# 5V_Main.net
KiCad netlist of a schematic drawn in Altium Designer
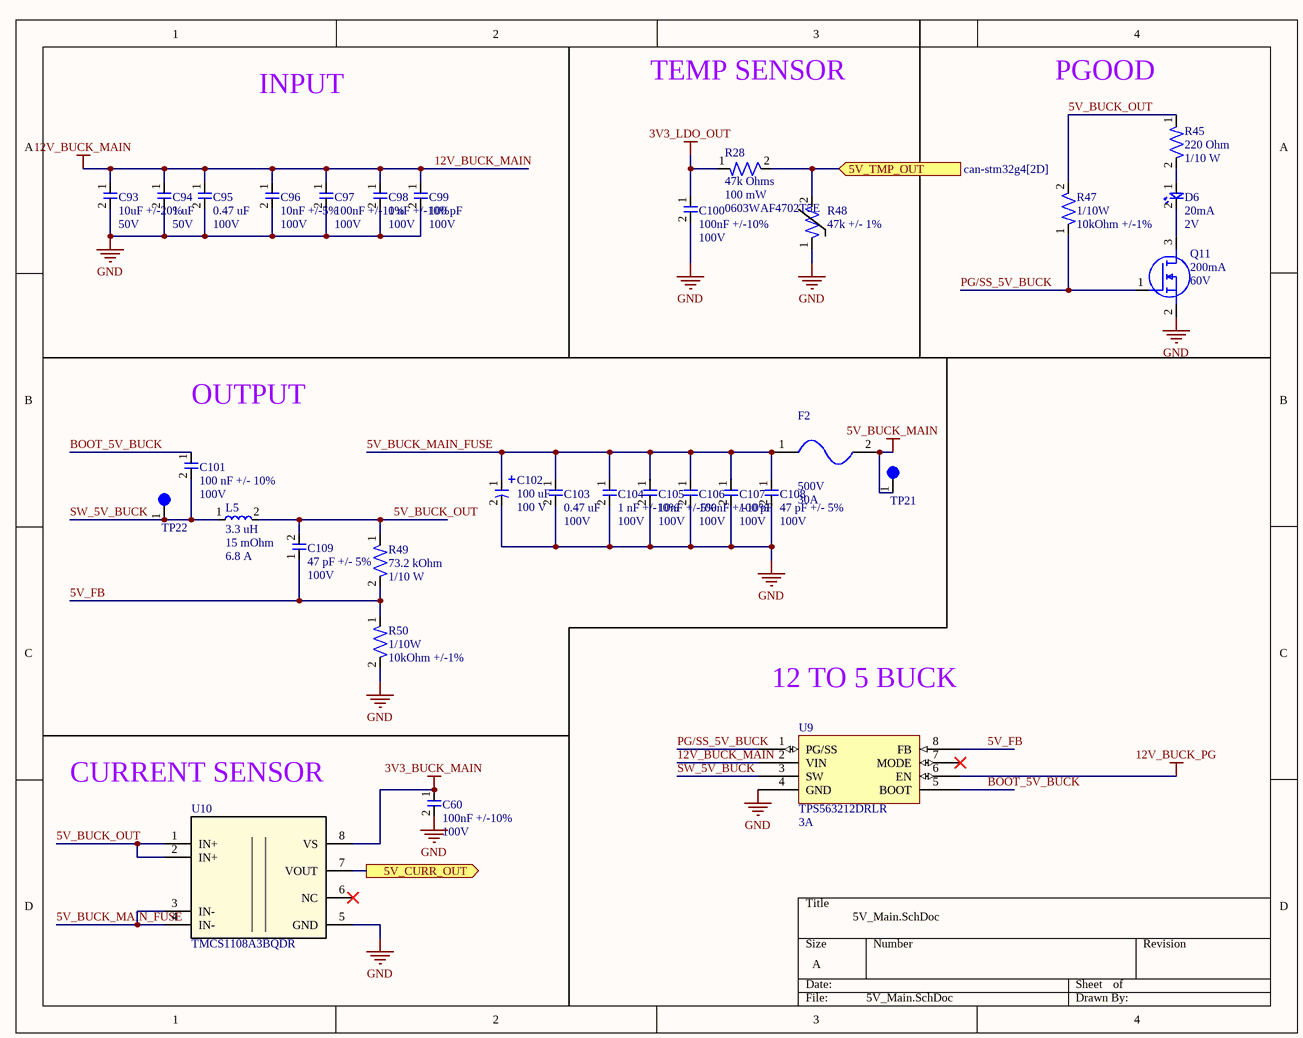
[diagram p0: 5V_Main.SchDoc]

(export (version "E")
  (design (tool "Eeschema 10.0.6"))
  (components
    (comp (ref "C60")
      (value "CC0603KRX7R0BB104")
      (footprint "CAP-0603")
      (description "CAP CER 0.1UF 100V X7R 0603")
      (fields
        (field (name "MANUFACTURER") "YAGEO")
        (field (name "CAPACITANCE") "100nF +/-10%")
        (field (name "VOLTAGE RATING") "100V")
      )
      (libsource (lib "MasterLib") (part "CAP-100N-0001"))
    )
    (comp (ref "C93")
      (value "CL31B106KBHNNNE")
      (footprint "CAP-1206")
      (description "10 µF ±10% 50V Ceramic Capacitor X7R 1206 (3216 Metric)")
      (fields
        (field (name "MANUFACTURER") "Samsung Electro-Mechanics")
        (field (name "CAPACITANCE") "10uF +/-20%")
        (field (name "VOLTAGE RATING") "50V")
      )
      (libsource (lib "MasterLib") (part "CAP-10U-0001"))
    )
    (comp (ref "C94")
      (value "UMK107AB7105KA-T")
      (footprint "CAP-0603")
      (description "1 µF ±10% 50V Ceramic Capacitor X7R 0603 (1608 Metric)")
      (fields (field (name "CAPACITANCE") "1 uF") (field (name "VOLTAGE") "50V"))
      (libsource (lib "MasterLib") (part "CAP-1U-0002"))
    )
    (comp (ref "C95")
      (value "KAM21KR72A474KL")
      (footprint "CAP-0805")
      (description "0.47 µF ±10% 100V Ceramic Capacitor X7R 0805 (2012 Metric)")
      (fields
        (field (name "TOLERANCE") "+/- 10%")
        (field (name "CAPACITANCE") "0.47 uF")
        (field (name "VOLTAGE") "100V")
      )
      (libsource (lib "MasterLib") (part "CAP-0.47U-0001"))
    )
    (comp (ref "C96")
      (value "C1608C0G2A103J080AC")
      (footprint "CAP-0603")
      (description "CAP CER 10000PF 100V C0G 0603")
      (fields
        (field (name "MANUFACTURER") "TDK Corporation")
        (field (name "CAPACITANCE") "10nF +/-5%")
        (field (name "VOLTAGE RATING") "100V")
      )
      (libsource (lib "MasterLib") (part "CAP-10N-0002"))
    )
    (comp (ref "C97")
      (value "CC0603KRX7R0BB104")
      (footprint "CAP-0603")
      (description "CAP CER 0.1UF 100V X7R 0603")
      (fields
        (field (name "MANUFACTURER") "YAGEO")
        (field (name "CAPACITANCE") "100nF +/-10%")
        (field (name "VOLTAGE RATING") "100V")
      )
      (libsource (lib "MasterLib") (part "CAP-100N-0001"))
    )
    (comp (ref "C98")
      (value "C0603Y102K1RAC7867")
      (footprint "CAP-0603")
      (description "1000 pF ±10% 100V Ceramic Capacitor X7R 0603 (1608 Metric)")
      (fields (field (name "CAPACITANCE") "1 nF +/-10%") (field (name "VOLTAGE") "100V"))
      (libsource (lib "MasterLib") (part "CAP-1N-0001"))
    )
    (comp (ref "C99")
      (value "0603N101J101CT")
      (footprint "CAP-0603")
      (description "100 pF ±5% 100V Ceramic Capacitor C0G, NP0 0603 (1608 Metric)")
      (fields
        (field (name "TOLERANCE") "+/-5%")
        (field (name "CAPACITANCE") "100 pF")
        (field (name "VOLTAGE") "100V")
      )
      (libsource (lib "MasterLib") (part "CAP-100P-0002"))
    )
    (comp (ref "C100")
      (value "CC0603KRX7R0BB104")
      (footprint "CAP-0603")
      (description "CAP CER 0.1UF 100V X7R 0603")
      (fields
        (field (name "MANUFACTURER") "YAGEO")
        (field (name "CAPACITANCE") "100nF +/-10%")
        (field (name "VOLTAGE RATING") "100V")
      )
      (libsource (lib "MasterLib") (part "CAP-100N-0001"))
    )
    (comp (ref "C101")
      (value "CC0603KRX7R0BB104")
      (footprint "CAP-0603")
      (description "100V 100nF X7R ±10% 0603 Multilayer Ceramic Capacitors MLCC - SMD/SMT ROHS")
      (fields
        (field (name "JLC PART NUMBER") "C113803")
        (field (name "CAPACITANCE") "100 nF +/- 10%")
        (field (name "VOLTAGE") "100V")
      )
      (libsource (lib "MasterLib") (part "CAP-100N-0002-JLC"))
    )
    (comp (ref "C102")
      (value "100SEV100M12.5X16")
      (footprint "ELEC-100U-0001")
      (description "100 µF 100 V Aluminum Electrolytic Capacitors Radial, Can - SMD 2000 Hrs @ 85°C")
      (fields
        (field (name "MANUFACTURER") "Rubycon")
        (field (name "TOLERANCE") "+/- 20%")
        (field (name "CAPACITANCE") "100 uF")
        (field (name "VOLTAGE") "100 V")
      )
      (libsource (lib "MasterLib") (part "ELEC-100U-0001"))
    )
    (comp (ref "C103")
      (value "KAM21KR72A474KL")
      (footprint "CAP-0805")
      (description "0.47 µF ±10% 100V Ceramic Capacitor X7R 0805 (2012 Metric)")
      (fields
        (field (name "TOLERANCE") "+/- 10%")
        (field (name "CAPACITANCE") "0.47 uF")
        (field (name "VOLTAGE") "100V")
      )
      (libsource (lib "MasterLib") (part "CAP-0.47U-0001"))
    )
    (comp (ref "C104")
      (value "C0603Y102K1RAC7867")
      (footprint "CAP-0603")
      (description "1000 pF ±10% 100V Ceramic Capacitor X7R 0603 (1608 Metric)")
      (fields (field (name "CAPACITANCE") "1 nF +/-10%") (field (name "VOLTAGE") "100V"))
      (libsource (lib "MasterLib") (part "CAP-1N-0001"))
    )
    (comp (ref "C105")
      (value "C1608C0G2A103J080AC")
      (footprint "CAP-0603")
      (description "CAP CER 10000PF 100V C0G 0603")
      (fields
        (field (name "MANUFACTURER") "TDK Corporation")
        (field (name "CAPACITANCE") "10nF +/-5%")
        (field (name "VOLTAGE RATING") "100V")
      )
      (libsource (lib "MasterLib") (part "CAP-10N-0002"))
    )
    (comp (ref "C106")
      (value "CC0603KRX7R0BB104")
      (footprint "CAP-0603")
      (description "CAP CER 0.1UF 100V X7R 0603")
      (fields
        (field (name "MANUFACTURER") "YAGEO")
        (field (name "CAPACITANCE") "100nF +/-10%")
        (field (name "VOLTAGE RATING") "100V")
      )
      (libsource (lib "MasterLib") (part "CAP-100N-0001"))
    )
    (comp (ref "C107")
      (value "0603N101J101CT")
      (footprint "CAP-0603")
      (description "100 pF ±5% 100V Ceramic Capacitor C0G, NP0 0603 (1608 Metric)")
      (fields
        (field (name "TOLERANCE") "+/-5%")
        (field (name "CAPACITANCE") "100 pF")
        (field (name "VOLTAGE") "100V")
      )
      (libsource (lib "MasterLib") (part "CAP-100P-0002"))
    )
    (comp (ref "C108")
      (value "7447798111")
      (footprint "CAP-0603")
      (description "47 pF ±5% 100V Ceramic Capacitor C0G, NP0 0603 (1608 Metric)")
      (fields (field (name "CAPACITANCE") "47 pF +/- 5%") (field (name "VOLTAGE RATING") "100V"))
      (libsource (lib "MasterLib") (part "CAP-47P-0001"))
    )
    (comp (ref "C109")
      (value "7447798111")
      (footprint "CAP-0603")
      (description "47 pF ±5% 100V Ceramic Capacitor C0G, NP0 0603 (1608 Metric)")
      (fields (field (name "CAPACITANCE") "47 pF +/- 5%") (field (name "VOLTAGE RATING") "100V"))
      (libsource (lib "MasterLib") (part "CAP-47P-0001"))
    )
    (comp (ref "D6")
      (value "150060AS75000")
      (footprint "LED-0603")
      (description "CAP CER 0.1UF 100V X7R 0603")
      (fields
        (field (name "MANUFACTURER") "Wurth Electronik")
        (field (name "CURRENT RATING") "20mA")
        (field (name "VF") "2V")
      )
      (libsource (lib "MasterLib") (part "LED_Amber_0001"))
    )
    (comp (ref "F2")
      (value "3568")
      (footprint "FUSE-ATM-0001")
      (description "Fuse Holder 30 A 500V 1 Circuit Blade Through Hole")
      (fields (field (name "VOLTAGE RATING") "500V") (field (name "CURRENT") "30A"))
      (libsource (lib "MasterLib") (part "FUSE-ATM-0001"))
    )
    (comp (ref "L5")
      (value "SRR1240-3R3Y")
      (footprint "PWRIND-3.3U-0003")
      (description "3.3 µH Shielded Drum Core, Wirewound Inductor 6.8 A 15mOhm Max Nonstandard")
      (fields
        (field (name "TOLERANCE") "30%")
        (field (name "INDUCTANCE") "3.3 uH")
        (field (name "DCR") "15 mOhm")
        (field (name "DCI") "6.8 A")
      )
      (libsource (lib "MasterLib") (part "PWRIND-3.3U-0003"))
    )
    (comp (ref "Q11")
      (value "T2N7002AK,LM")
      (footprint "NMOS-SOT23-3")
      (description "MOSFET N-CH 60V 200MA SOT23")
      (fields
        (field (name "MANUFACTURER") "Toshiba")
        (field (name "ID-CONTINUOUS") "200mA")
        (field (name "VDS-MAX") "60V")
      )
      (libsource (lib "MasterLib") (part "NMOS-200MA-0001"))
    )
    (comp (ref "R28")
      (value "0603WAF4702T5E")
      (footprint "RES-0603")
      (description "100mW Thick Film Resistors 75V ±100ppm/℃ ±1% 47kΩ 0603 Chip Resistor - Surface Mount ROHS")
      (fields (field (name "POWER") "100mW"))
      (libsource (lib "MasterLib") (part "RES-47k-0001-JLC"))
    )
    (comp (ref "R45")
      (value "CRGCQ0603J220R")
      (footprint "RES-0603")
      (fields
        (field (name "TOLERANCE") "+/- 5%")
        (field (name "RESISTANCE") "220 Ohm")
        (field (name "POWER") "1/10 W")
      )
      (libsource (lib "MasterLib") (part "RES-220-003"))
    )
    (comp (ref "R47")
      (value "RC0603FR-0710KP")
      (footprint "RES-0603")
      (description "RES SMD 10K OHM 1% 1/10W 0603")
      (fields
        (field (name "MANUFACTURER") "YAGEO")
        (field (name "POWER RATING") "1/10W")
        (field (name "RESISTANCE") "10kOhm +/-1%")
      )
      (libsource (lib "MasterLib") (part "RES-10K-0002"))
    )
    (comp (ref "R48")
      (value "TMP6431DECR")
      (footprint "RES-0402")
      (description "PTC Thermistor 47 kOhms 0402 (1006 Metric)")
      (fields (field (name "MANUFACTURER") "Texas Instruments") (field (name "RESISTANCE") "47k +/- 1%"))
      (libsource (lib "MasterLib") (part "THERM-47K-0001"))
    )
    (comp (ref "R49")
      (value "RC0603FR-0773K2L")
      (footprint "RES-0603")
      (description "73.2 kOhms ±1% 0.1W, 1/10W Chip Resistor 0603 (1608 Metric) Moisture Resistant Thick Film")
      (fields
        (field (name "TOLERANCE") "1%")
        (field (name "RESISTANCE") "73.2 kOhm")
        (field (name "POWER") "1/10 W")
      )
      (libsource (lib "MasterLib") (part "RES-73.2K-0001"))
    )
    (comp (ref "R50")
      (value "RC0603FR-0710KP")
      (footprint "RES-0603")
      (description "RES SMD 10K OHM 1% 1/10W 0603")
      (fields
        (field (name "MANUFACTURER") "YAGEO")
        (field (name "POWER RATING") "1/10W")
        (field (name "RESISTANCE") "10kOhm +/-1%")
      )
      (libsource (lib "MasterLib") (part "RES-10K-0002"))
    )
    (comp (ref "TP21")
      (value "5003")
      (footprint "TEST-POINT-0001")
      (description "Oranange PC Test Point, Miniature Phoisphor Bronze Silver Plating Through Hole Mounting Type")
      (libsource (lib "MasterLib") (part "TEST-POINT-0001"))
    )
    (comp (ref "TP22")
      (value "5003")
      (footprint "TEST-POINT-0001")
      (description "Oranange PC Test Point, Miniature Phoisphor Bronze Silver Plating Through Hole Mounting Type")
      (libsource (lib "MasterLib") (part "TEST-POINT-0001"))
    )
    (comp (ref "U9")
      (value "TPS563212DRLR")
      (footprint "IC-SOT583")
      (description "Buck Switching Regulator IC Positive Adjustable 0.6V 1 Output 3A SOT-583")
      (fields (field (name "MANUFACTURER") "Texaas Instruments") (field (name "CURRENT") "3A"))
      (libsource (lib "MasterLib") (part "IC-BUCK-0008"))
    )
    (comp (ref "U10")
      (value "TMCS1108A3BQDR")
      (footprint "D0008A-IPC_A")
      (libsource (lib "MasterLib") (part "IC-CURRENT-0005"))
    )
  )
  (nets
    (net (code "1") (name "/5V_BUCK_MAIN_FUSE") (class "Default")
      (node (ref "C102") (pin "1") (pinfunction "1_1") (pintype "passive"))
      (node (ref "C103") (pin "1") (pinfunction "1_1") (pintype "passive"))
      (node (ref "C104") (pin "1") (pinfunction "1_1") (pintype "passive"))
      (node (ref "C105") (pin "1") (pinfunction "1_1") (pintype "passive"))
      (node (ref "C106") (pin "1") (pinfunction "1_1") (pintype "passive"))
      (node (ref "C107") (pin "1") (pinfunction "1_1") (pintype "passive"))
      (node (ref "C108") (pin "1") (pinfunction "1_1") (pintype "passive"))
      (node (ref "F2") (pin "1") (pinfunction "0_1") (pintype "passive"))
      (node (ref "U10") (pin "3") (pinfunction "IN-_3") (pintype "passive"))
      (node (ref "U10") (pin "4") (pinfunction "IN-_4") (pintype "passive"))
    )
    (net (code "2") (name "/5V_BUCK_OUT") (class "Default")
      (node (ref "C109") (pin "2") (pinfunction "2_2") (pintype "passive"))
      (node (ref "L5") (pin "2") (pinfunction "2_2") (pintype "passive"))
      (node (ref "R45") (pin "1") (pinfunction "1_1") (pintype "passive"))
      (node (ref "R47") (pin "2") (pinfunction "2_2") (pintype "passive"))
      (node (ref "R49") (pin "1") (pinfunction "1_1") (pintype "passive"))
      (node (ref "U10") (pin "1") (pinfunction "IN+_1") (pintype "passive"))
      (node (ref "U10") (pin "2") (pinfunction "IN+_2") (pintype "passive"))
    )
    (net (code "3") (name "/5V_CURR_OUT") (class "Default")
      (node (ref "U10") (pin "7") (pinfunction "VOUT_7") (pintype "passive"))
    )
    (net (code "4") (name "/5V_FB") (class "Default")
      (node (ref "C109") (pin "1") (pinfunction "1_1") (pintype "passive"))
      (node (ref "R49") (pin "2") (pinfunction "2_2") (pintype "passive"))
      (node (ref "R50") (pin "1") (pinfunction "1_1") (pintype "passive"))
      (node (ref "U9") (pin "8") (pinfunction "FB_8") (pintype "input"))
    )
    (net (code "5") (name "/5V_TMP_OUT") (class "Default")
      (node (ref "R28") (pin "2") (pinfunction "2_2") (pintype "passive"))
      (node (ref "R48") (pin "2") (pinfunction "2_2") (pintype "passive"))
    )
    (net (code "6") (name "/BOOT_5V_BUCK") (class "Default")
      (node (ref "C101") (pin "1") (pinfunction "1_1") (pintype "passive"))
      (node (ref "U9") (pin "5") (pinfunction "BOOT_5") (pintype "power_in"))
    )
    (net (code "7") (name "/PG{slash}SS_5V_BUCK") (class "Default")
      (node (ref "Q11") (pin "1") (pinfunction "G_1") (pintype "passive"))
      (node (ref "R47") (pin "1") (pinfunction "1_1") (pintype "passive"))
      (node (ref "U9") (pin "1") (pinfunction "PG/SS_1") (pintype "bidirectional"))
    )
    (net (code "8") (name "/SW_5V_BUCK") (class "Default")
      (node (ref "C101") (pin "2") (pinfunction "2_2") (pintype "passive"))
      (node (ref "L5") (pin "1") (pinfunction "1_1") (pintype "passive"))
      (node (ref "TP22") (pin "1") (pinfunction "0_1") (pintype "passive"))
      (node (ref "U9") (pin "3") (pinfunction "SW_3") (pintype "power_in"))
    )
    (net (code "9") (name "3V3_BUCK_MAIN") (class "Default")
      (node (ref "C60") (pin "1") (pinfunction "1_1") (pintype "passive"))
      (node (ref "U10") (pin "8") (pinfunction "VS_8") (pintype "power_in"))
    )
    (net (code "10") (name "3V3_LDO_OUT") (class "Default")
      (node (ref "C100") (pin "1") (pinfunction "1_1") (pintype "passive"))
      (node (ref "R28") (pin "1") (pinfunction "1_1") (pintype "passive"))
    )
    (net (code "11") (name "5V_BUCK_MAIN") (class "Default")
      (node (ref "F2") (pin "2") (pinfunction "1_2") (pintype "passive"))
      (node (ref "TP21") (pin "1") (pinfunction "0_1") (pintype "passive"))
    )
    (net (code "12") (name "12V_BUCK_MAIN") (class "Default")
      (node (ref "C93") (pin "1") (pinfunction "1_1") (pintype "passive"))
      (node (ref "C94") (pin "1") (pinfunction "1_1") (pintype "passive"))
      (node (ref "C95") (pin "1") (pinfunction "1_1") (pintype "passive"))
      (node (ref "C96") (pin "1") (pinfunction "1_1") (pintype "passive"))
      (node (ref "C97") (pin "1") (pinfunction "1_1") (pintype "passive"))
      (node (ref "C98") (pin "1") (pinfunction "1_1") (pintype "passive"))
      (node (ref "C99") (pin "1") (pinfunction "1_1") (pintype "passive"))
      (node (ref "U9") (pin "2") (pinfunction "VIN_2") (pintype "power_in"))
    )
    (net (code "13") (name "12V_BUCK_PG") (class "Default")
      (node (ref "U9") (pin "6") (pinfunction "EN_6") (pintype "bidirectional"))
    )
    (net (code "14") (name "GND") (class "Default")
      (node (ref "C100") (pin "2") (pinfunction "2_2") (pintype "passive"))
      (node (ref "C102") (pin "2") (pinfunction "2_2") (pintype "passive"))
      (node (ref "C103") (pin "2") (pinfunction "2_2") (pintype "passive"))
      (node (ref "C104") (pin "2") (pinfunction "2_2") (pintype "passive"))
      (node (ref "C105") (pin "2") (pinfunction "2_2") (pintype "passive"))
      (node (ref "C106") (pin "2") (pinfunction "2_2") (pintype "passive"))
      (node (ref "C107") (pin "2") (pinfunction "2_2") (pintype "passive"))
      (node (ref "C108") (pin "2") (pinfunction "2_2") (pintype "passive"))
      (node (ref "C60") (pin "2") (pinfunction "2_2") (pintype "passive"))
      (node (ref "C93") (pin "2") (pinfunction "2_2") (pintype "passive"))
      (node (ref "C94") (pin "2") (pinfunction "2_2") (pintype "passive"))
      (node (ref "C95") (pin "2") (pinfunction "2_2") (pintype "passive"))
      (node (ref "C96") (pin "2") (pinfunction "2_2") (pintype "passive"))
      (node (ref "C97") (pin "2") (pinfunction "2_2") (pintype "passive"))
      (node (ref "C98") (pin "2") (pinfunction "2_2") (pintype "passive"))
      (node (ref "C99") (pin "2") (pinfunction "2_2") (pintype "passive"))
      (node (ref "Q11") (pin "2") (pinfunction "S_2") (pintype "passive"))
      (node (ref "R48") (pin "1") (pinfunction "1_1") (pintype "passive"))
      (node (ref "R50") (pin "2") (pinfunction "2_2") (pintype "passive"))
      (node (ref "U10") (pin "5") (pinfunction "GND_5") (pintype "power_in"))
      (node (ref "U9") (pin "4") (pinfunction "GND_4") (pintype "power_in"))
    )
    (net (code "15") (name "Net-(D6-Pad1)") (class "Default")
      (node (ref "D6") (pin "1") (pinfunction "1_1") (pintype "passive"))
      (node (ref "R45") (pin "2") (pinfunction "2_2") (pintype "passive"))
    )
    (net (code "16") (name "Net-(Q11-D)") (class "Default")
      (node (ref "D6") (pin "2") (pinfunction "2_2") (pintype "passive"))
      (node (ref "Q11") (pin "3") (pinfunction "D_3") (pintype "passive"))
    )
    (net (code "17") (name "unconnected-(U9-MODE-Pad7)") (class "Default")
      (node (ref "U9") (pin "7") (pinfunction "MODE_7") (pintype "bidirectional+no_connect"))
    )
    (net (code "18") (name "unconnected-(U10-NC-Pad6)") (class "Default")
      (node (ref "U10") (pin "6") (pinfunction "NC_6") (pintype "passive+no_connect"))
    )
  )
)
